# Grove_-_SPDT_Relay_30A_v1_0.net
KiCad netlist of a schematic drawn in EAGLE
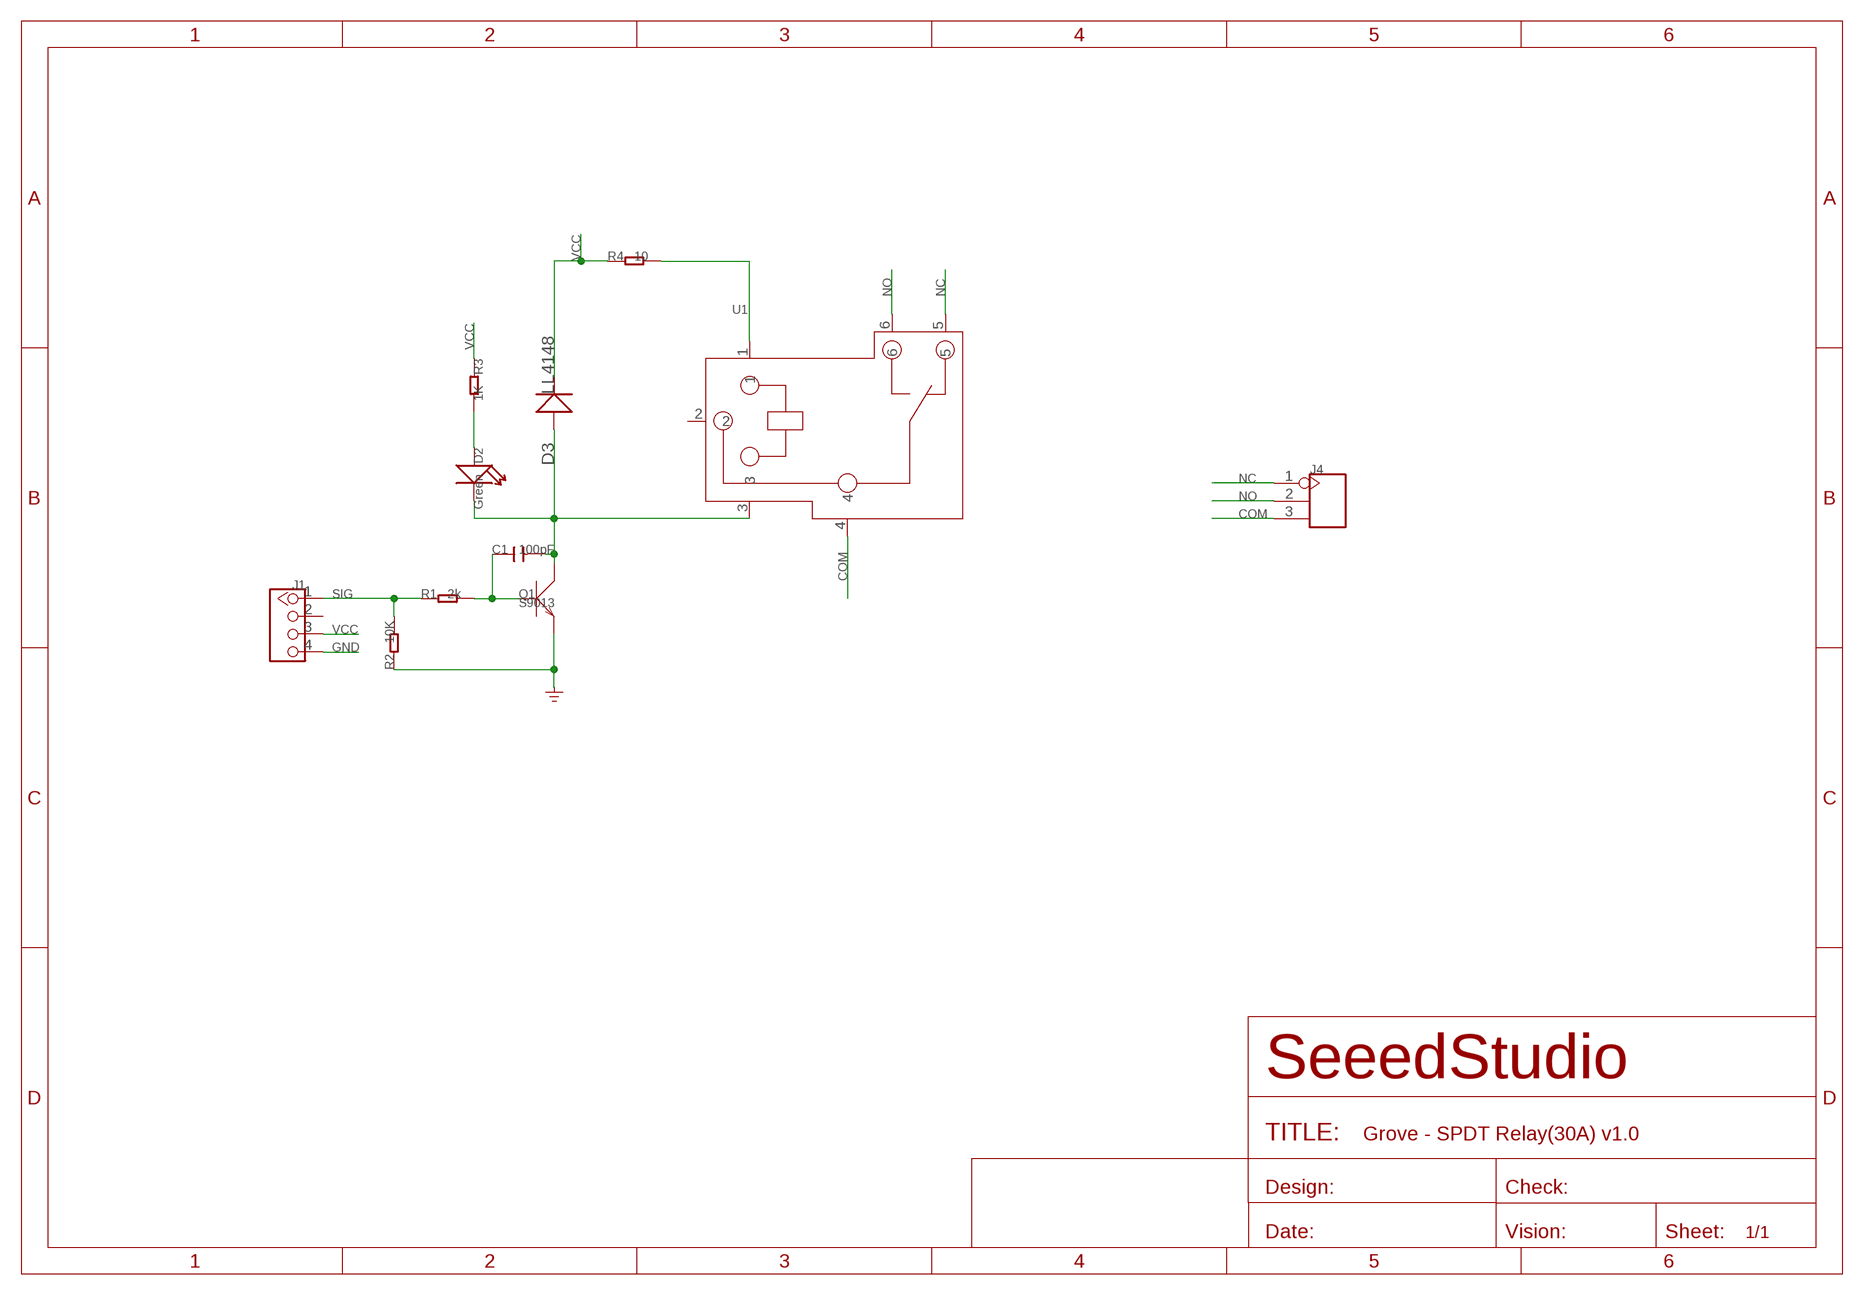
[diagram p0: schematic, sheet 1]

(export (version "E")
  (design (tool "Eeschema 10.0.6"))
  (components
    (comp (ref "C1")
      (value "100pF")
      (footprint "eagle-import:C0603")
      (libsource (lib "eagle-import") (part "C-0603"))
    )
    (comp (ref "D2")
      (value "Green")
      (footprint "eagle-import:LED-0603")
      (libsource (lib "eagle-import") (part "LED'0603'"))
    )
    (comp (ref "D3")
      (value "LL4148")
      (footprint "eagle-import:DO-35-SMD")
      (libsource (lib "eagle-import") (part "D'1N4148-SMD'"))
    )
    (comp (ref "J1")
      (value "TWIG-4P-2.0-2.0")
      (footprint "eagle-import:4P-2.0")
      (libsource (lib "eagle-import") (part "TWIG-4P-2.0-2.0"))
    )
    (comp (ref "J4")
      (value "SCREW-TERMINAL-3P'5.08'")
      (footprint "eagle-import:3P-5.08")
      (libsource (lib "eagle-import") (part "SCREW-TERMINAL-3P'5.08'"))
    )
    (comp (ref "Q1")
      (value "S9013")
      (footprint "eagle-import:SOT23")
      (libsource (lib "eagle-import") (part "TRANSISTOR-NPN-SOT23"))
    )
    (comp (ref "R1")
      (value "2k")
      (footprint "eagle-import:R0603")
      (libsource (lib "eagle-import") (part "R-0603"))
    )
    (comp (ref "R2")
      (value "10K")
      (footprint "eagle-import:R0603")
      (libsource (lib "eagle-import") (part "R-0603"))
    )
    (comp (ref "R3")
      (value "1K")
      (footprint "eagle-import:R0603")
      (libsource (lib "eagle-import") (part "R-0603"))
    )
    (comp (ref "R4")
      (value "10")
      (footprint "eagle-import:R0603")
      (libsource (lib "eagle-import") (part "R-0603"))
    )
    (comp (ref "U1")
      (value "RELAY-SLA-05VDC-SL-C")
      (footprint "eagle-import:6P-19.8H")
      (libsource (lib "eagle-import") (part "RELAY-SLA-05VDC-SL-C"))
    )
  )
  (nets
    (net (code "1") (name "/COM") (class "Default")
      (node (ref "J4") (pin "3") (pinfunction "P$3_3") (pintype "bidirectional"))
      (node (ref "U1") (pin "4") (pinfunction "4_4") (pintype "bidirectional"))
    )
    (net (code "2") (name "/NC") (class "Default")
      (node (ref "J4") (pin "1") (pinfunction "P$1_1") (pintype "bidirectional"))
      (node (ref "U1") (pin "5") (pinfunction "5_5") (pintype "bidirectional"))
    )
    (net (code "3") (name "/NO") (class "Default")
      (node (ref "J4") (pin "2") (pinfunction "P$2_2") (pintype "bidirectional"))
      (node (ref "U1") (pin "6") (pinfunction "6_6") (pintype "bidirectional"))
    )
    (net (code "4") (name "/SIG") (class "Default")
      (node (ref "J1") (pin "1") (pinfunction "1_1") (pintype "bidirectional"))
      (node (ref "R1") (pin "1") (pinfunction "1_1") (pintype "passive"))
      (node (ref "R2") (pin "2") (pinfunction "2_2") (pintype "passive"))
    )
    (net (code "5") (name "/VCC") (class "Default")
      (node (ref "D3") (pin "C") (pinfunction "-_C") (pintype "passive"))
      (node (ref "J1") (pin "3") (pinfunction "3_3") (pintype "bidirectional"))
      (node (ref "R3") (pin "1") (pinfunction "1_1") (pintype "passive"))
      (node (ref "R4") (pin "1") (pinfunction "1_1") (pintype "passive"))
    )
    (net (code "6") (name "GND_POWER") (class "Default")
      (node (ref "J1") (pin "4") (pinfunction "4_4") (pintype "bidirectional"))
      (node (ref "Q1") (pin "2") (pinfunction "E_2") (pintype "passive"))
      (node (ref "R2") (pin "1") (pinfunction "1_1") (pintype "passive"))
    )
    (net (code "7") (name "Net-(D2-Pad+)") (class "Default")
      (node (ref "D2") (pin "+") (pinfunction "+_+") (pintype "passive"))
      (node (ref "R3") (pin "2") (pinfunction "2_2") (pintype "passive"))
    )
    (net (code "8") (name "Net-(D3-+)") (class "Default")
      (node (ref "C1") (pin "2") (pinfunction "2_2") (pintype "passive"))
      (node (ref "D2") (pin "-") (pinfunction "-_-") (pintype "passive"))
      (node (ref "D3") (pin "A") (pinfunction "+_A") (pintype "passive"))
      (node (ref "Q1") (pin "3") (pinfunction "C_3") (pintype "passive"))
      (node (ref "U1") (pin "3") (pinfunction "3_3") (pintype "bidirectional"))
    )
    (net (code "9") (name "Net-(Q1-B)") (class "Default")
      (node (ref "C1") (pin "1") (pinfunction "1_1") (pintype "passive"))
      (node (ref "Q1") (pin "1") (pinfunction "B_1") (pintype "passive"))
      (node (ref "R1") (pin "2") (pinfunction "2_2") (pintype "passive"))
    )
    (net (code "10") (name "Net-(R4-Pad2)") (class "Default")
      (node (ref "R4") (pin "2") (pinfunction "2_2") (pintype "passive"))
      (node (ref "U1") (pin "1") (pinfunction "1_1") (pintype "bidirectional"))
    )
    (net (code "11") (name "unconnected-(J1-Pad2)") (class "Default")
      (node (ref "J1") (pin "2") (pinfunction "2_2") (pintype "bidirectional"))
    )
    (net (code "12") (name "unconnected-(U1-Pad2)") (class "Default")
      (node (ref "U1") (pin "2") (pinfunction "2_2") (pintype "bidirectional"))
    )
  )
)
